# TDA2822M.net
KiCad netlist of a schematic drawn in EAGLE
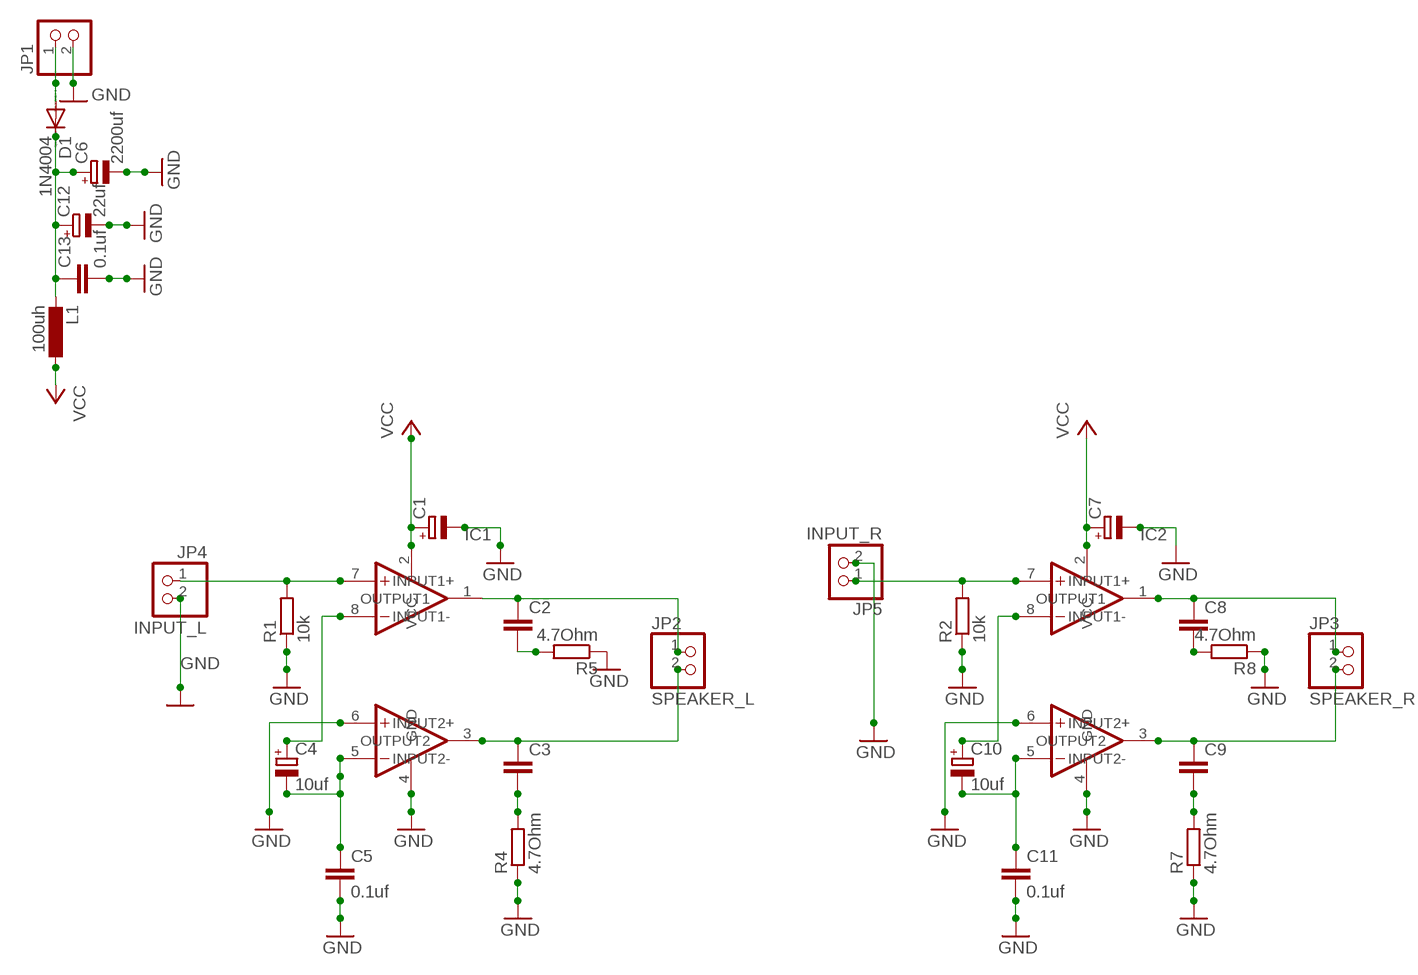
[diagram p0: schematic, sheet 1]

(export (version "E")
  (design (tool "Eeschema 10.0.6"))
  (components
    (comp (ref "C1")
      (value "CPOL-EUE2.5-7")
      (footprint "eagle-import:E2,5-7")
      (libsource (lib "eagle-import") (part "CPOL-EUE2.5-7"))
    )
    (comp (ref "C2")
      (value "C-EU025_050-035X075")
      (footprint "eagle-import:C025_050-035X075")
      (libsource (lib "eagle-import") (part "C-EU025_050-035X075"))
    )
    (comp (ref "C3")
      (value "C-EU025_050-035X075")
      (footprint "eagle-import:C025_050-035X075")
      (libsource (lib "eagle-import") (part "C-EU025_050-035X075"))
    )
    (comp (ref "C4")
      (value "10uf")
      (footprint "eagle-import:E2,5-7")
      (libsource (lib "eagle-import") (part "CPOL-EUE2.5-7"))
    )
    (comp (ref "C5")
      (value "0.1uf")
      (footprint "eagle-import:C025_050-035X075")
      (libsource (lib "eagle-import") (part "C-EU025_050-035X075"))
    )
    (comp (ref "C6")
      (value "2200uf")
      (footprint "eagle-import:E3,5-8")
      (libsource (lib "eagle-import") (part "CPOL-EUE3.5-8"))
    )
    (comp (ref "C7")
      (value "CPOL-EUE2.5-7")
      (footprint "eagle-import:E2,5-7")
      (libsource (lib "eagle-import") (part "CPOL-EUE2.5-7"))
    )
    (comp (ref "C8")
      (value "C-EU025_050-035X075")
      (footprint "eagle-import:C025_050-035X075")
      (libsource (lib "eagle-import") (part "C-EU025_050-035X075"))
    )
    (comp (ref "C9")
      (value "C-EU025_050-035X075")
      (footprint "eagle-import:C025_050-035X075")
      (libsource (lib "eagle-import") (part "C-EU025_050-035X075"))
    )
    (comp (ref "C10")
      (value "10uf")
      (footprint "eagle-import:E2,5-7")
      (libsource (lib "eagle-import") (part "CPOL-EUE2.5-7"))
    )
    (comp (ref "C11")
      (value "0.1uf")
      (footprint "eagle-import:C025_050-035X075")
      (libsource (lib "eagle-import") (part "C-EU025_050-035X075"))
    )
    (comp (ref "C12")
      (value "22uf")
      (footprint "eagle-import:E3,5-8")
      (libsource (lib "eagle-import") (part "CPOL-EUE3.5-8"))
    )
    (comp (ref "C13")
      (value "0.1uf")
      (footprint "eagle-import:C2.5-3")
      (libsource (lib "eagle-import") (part "C2,5-3"))
    )
    (comp (ref "D1")
      (value "1N4004")
      (footprint "eagle-import:DO41-10")
      (libsource (lib "eagle-import") (part "1N4004"))
    )
    (comp (ref "IC1")
      (value "TDA2822M")
      (footprint "eagle-import:DIL8")
      (libsource (lib "eagle-import") (part "TDA2822M"))
    )
    (comp (ref "IC2")
      (value "TDA2822M")
      (footprint "eagle-import:DIL8")
      (libsource (lib "eagle-import") (part "TDA2822M"))
    )
    (comp (ref "JP1")
      (value "PINHD-1X2")
      (footprint "eagle-import:1X02")
      (libsource (lib "eagle-import") (part "PINHD-1X2"))
    )
    (comp (ref "JP2")
      (value "SPEAKER_L")
      (footprint "eagle-import:1X02")
      (libsource (lib "eagle-import") (part "PINHD-1X2"))
    )
    (comp (ref "JP3")
      (value "SPEAKER_R")
      (footprint "eagle-import:1X02")
      (libsource (lib "eagle-import") (part "PINHD-1X2"))
    )
    (comp (ref "JP4")
      (value "INPUT_L")
      (footprint "eagle-import:1X02")
      (libsource (lib "eagle-import") (part "PINHD-1X2"))
    )
    (comp (ref "JP5")
      (value "INPUT_R")
      (footprint "eagle-import:1X02")
      (libsource (lib "eagle-import") (part "PINHD-1X2"))
    )
    (comp (ref "L1")
      (value "100uh")
      (footprint "eagle-import:0207_10")
      (libsource (lib "eagle-import") (part "L-EU0207/10"))
    )
    (comp (ref "R1")
      (value "10k")
      (footprint "eagle-import:0207_10")
      (libsource (lib "eagle-import") (part "R-EU_0207/10"))
    )
    (comp (ref "R2")
      (value "10k")
      (footprint "eagle-import:0207_10")
      (libsource (lib "eagle-import") (part "R-EU_0207/10"))
    )
    (comp (ref "R4")
      (value "4.7Ohm")
      (footprint "eagle-import:0207_10")
      (libsource (lib "eagle-import") (part "R-EU_0207/10"))
    )
    (comp (ref "R5")
      (value "4.7Ohm")
      (footprint "eagle-import:0207_10")
      (libsource (lib "eagle-import") (part "R-EU_0207/10"))
    )
    (comp (ref "R7")
      (value "4.7Ohm")
      (footprint "eagle-import:0207_10")
      (libsource (lib "eagle-import") (part "R-EU_0207/10"))
    )
    (comp (ref "R8")
      (value "4.7Ohm")
      (footprint "eagle-import:0207_10")
      (libsource (lib "eagle-import") (part "R-EU_0207/10"))
    )
  )
  (nets
    (net (code "1") (name "GND") (class "Default")
      (node (ref "C1") (pin "-") (pinfunction "-_-") (pintype "passive"))
      (node (ref "C11") (pin "2") (pinfunction "2_2") (pintype "passive"))
      (node (ref "C12") (pin "-") (pinfunction "-_-") (pintype "passive"))
      (node (ref "C13") (pin "2") (pinfunction "2_2") (pintype "passive"))
      (node (ref "C5") (pin "2") (pinfunction "2_2") (pintype "passive"))
      (node (ref "C6") (pin "-") (pinfunction "-_-") (pintype "passive"))
      (node (ref "C7") (pin "-") (pinfunction "-_-") (pintype "passive"))
      (node (ref "IC1") (pin "4") (pinfunction "GND_4") (pintype "bidirectional"))
      (node (ref "IC1") (pin "6") (pinfunction "INPUT2+_6") (pintype "bidirectional"))
      (node (ref "IC2") (pin "4") (pinfunction "GND_4") (pintype "bidirectional"))
      (node (ref "IC2") (pin "6") (pinfunction "INPUT2+_6") (pintype "bidirectional"))
      (node (ref "JP1") (pin "2") (pinfunction "2_2") (pintype "passive"))
      (node (ref "JP4") (pin "2") (pinfunction "2_2") (pintype "passive"))
      (node (ref "JP5") (pin "2") (pinfunction "2_2") (pintype "passive"))
      (node (ref "R1") (pin "1") (pinfunction "1_1") (pintype "passive"))
      (node (ref "R2") (pin "1") (pinfunction "1_1") (pintype "passive"))
      (node (ref "R4") (pin "1") (pinfunction "1_1") (pintype "passive"))
      (node (ref "R5") (pin "1") (pinfunction "1_1") (pintype "passive"))
      (node (ref "R7") (pin "1") (pinfunction "1_1") (pintype "passive"))
      (node (ref "R8") (pin "1") (pinfunction "1_1") (pintype "passive"))
    )
    (net (code "2") (name "Net-(C2-Pad2)") (class "Default")
      (node (ref "C2") (pin "2") (pinfunction "2_2") (pintype "passive"))
      (node (ref "R5") (pin "2") (pinfunction "2_2") (pintype "passive"))
    )
    (net (code "3") (name "Net-(C3-Pad2)") (class "Default")
      (node (ref "C3") (pin "2") (pinfunction "2_2") (pintype "passive"))
      (node (ref "R4") (pin "2") (pinfunction "2_2") (pintype "passive"))
    )
    (net (code "4") (name "Net-(C8-Pad2)") (class "Default")
      (node (ref "C8") (pin "2") (pinfunction "2_2") (pintype "passive"))
      (node (ref "R8") (pin "2") (pinfunction "2_2") (pintype "passive"))
    )
    (net (code "5") (name "Net-(C9-Pad2)") (class "Default")
      (node (ref "C9") (pin "2") (pinfunction "2_2") (pintype "passive"))
      (node (ref "R7") (pin "2") (pinfunction "2_2") (pintype "passive"))
    )
    (net (code "6") (name "Net-(C12-Pad+)") (class "Default")
      (node (ref "C12") (pin "+") (pinfunction "+_+") (pintype "passive"))
      (node (ref "C13") (pin "1") (pinfunction "1_1") (pintype "passive"))
      (node (ref "C6") (pin "+") (pinfunction "+_+") (pintype "passive"))
      (node (ref "D1") (pin "C") (pinfunction "C_C") (pintype "passive"))
      (node (ref "L1") (pin "2") (pinfunction "2_2") (pintype "passive"))
    )
    (net (code "7") (name "Net-(D1-PadA)") (class "Default")
      (node (ref "D1") (pin "A") (pinfunction "A_A") (pintype "passive"))
      (node (ref "JP1") (pin "1") (pinfunction "1_1") (pintype "passive"))
    )
    (net (code "8") (name "Net-(IC1-INPUT1+)") (class "Default")
      (node (ref "IC1") (pin "7") (pinfunction "INPUT1+_7") (pintype "bidirectional"))
      (node (ref "JP4") (pin "1") (pinfunction "1_1") (pintype "passive"))
      (node (ref "R1") (pin "2") (pinfunction "2_2") (pintype "passive"))
    )
    (net (code "9") (name "Net-(IC1-INPUT1-)") (class "Default")
      (node (ref "C4") (pin "+") (pinfunction "+_+") (pintype "passive"))
      (node (ref "IC1") (pin "8") (pinfunction "INPUT1-_8") (pintype "bidirectional"))
    )
    (net (code "10") (name "Net-(IC1-INPUT2-)") (class "Default")
      (node (ref "C4") (pin "-") (pinfunction "-_-") (pintype "passive"))
      (node (ref "C5") (pin "1") (pinfunction "1_1") (pintype "passive"))
      (node (ref "IC1") (pin "5") (pinfunction "INPUT2-_5") (pintype "bidirectional"))
    )
    (net (code "11") (name "Net-(IC1-OUTPUT1)") (class "Default")
      (node (ref "C2") (pin "1") (pinfunction "1_1") (pintype "passive"))
      (node (ref "IC1") (pin "1") (pinfunction "OUTPUT1_1") (pintype "bidirectional"))
      (node (ref "JP2") (pin "1") (pinfunction "1_1") (pintype "passive"))
    )
    (net (code "12") (name "Net-(IC1-OUTPUT2)") (class "Default")
      (node (ref "C3") (pin "1") (pinfunction "1_1") (pintype "passive"))
      (node (ref "IC1") (pin "3") (pinfunction "OUTPUT2_3") (pintype "bidirectional"))
      (node (ref "JP2") (pin "2") (pinfunction "2_2") (pintype "passive"))
    )
    (net (code "13") (name "Net-(IC2-INPUT1+)") (class "Default")
      (node (ref "IC2") (pin "7") (pinfunction "INPUT1+_7") (pintype "bidirectional"))
      (node (ref "JP5") (pin "1") (pinfunction "1_1") (pintype "passive"))
      (node (ref "R2") (pin "2") (pinfunction "2_2") (pintype "passive"))
    )
    (net (code "14") (name "Net-(IC2-INPUT1-)") (class "Default")
      (node (ref "C10") (pin "+") (pinfunction "+_+") (pintype "passive"))
      (node (ref "IC2") (pin "8") (pinfunction "INPUT1-_8") (pintype "bidirectional"))
    )
    (net (code "15") (name "Net-(IC2-INPUT2-)") (class "Default")
      (node (ref "C10") (pin "-") (pinfunction "-_-") (pintype "passive"))
      (node (ref "C11") (pin "1") (pinfunction "1_1") (pintype "passive"))
      (node (ref "IC2") (pin "5") (pinfunction "INPUT2-_5") (pintype "bidirectional"))
    )
    (net (code "16") (name "Net-(IC2-OUTPUT1)") (class "Default")
      (node (ref "C8") (pin "1") (pinfunction "1_1") (pintype "passive"))
      (node (ref "IC2") (pin "1") (pinfunction "OUTPUT1_1") (pintype "bidirectional"))
      (node (ref "JP3") (pin "1") (pinfunction "1_1") (pintype "passive"))
    )
    (net (code "17") (name "Net-(IC2-OUTPUT2)") (class "Default")
      (node (ref "C9") (pin "1") (pinfunction "1_1") (pintype "passive"))
      (node (ref "IC2") (pin "3") (pinfunction "OUTPUT2_3") (pintype "bidirectional"))
      (node (ref "JP3") (pin "2") (pinfunction "2_2") (pintype "passive"))
    )
    (net (code "18") (name "VCC") (class "Default")
      (node (ref "C1") (pin "+") (pinfunction "+_+") (pintype "passive"))
      (node (ref "C7") (pin "+") (pinfunction "+_+") (pintype "passive"))
      (node (ref "IC1") (pin "2") (pinfunction "VCC_2") (pintype "bidirectional"))
      (node (ref "IC2") (pin "2") (pinfunction "VCC_2") (pintype "bidirectional"))
      (node (ref "L1") (pin "1") (pinfunction "1_1") (pintype "passive"))
    )
  )
)
